# led.net
KiCad netlist of a schematic drawn in Altium Designer
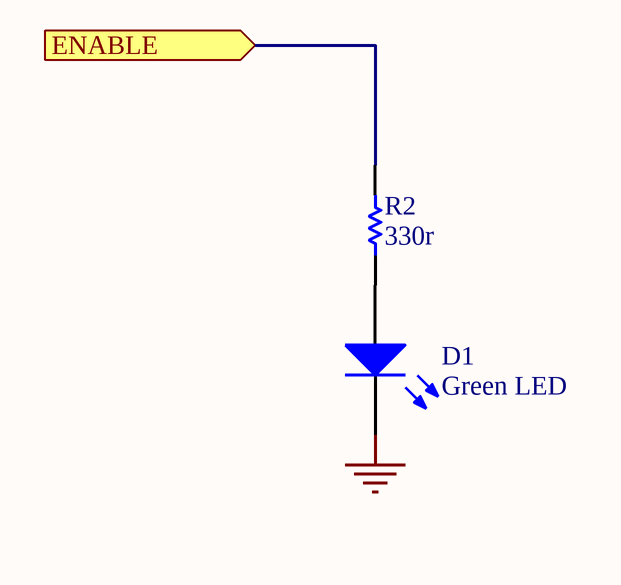
[diagram p0: led.SchDoc]

(export (version "E")
  (design (tool "Eeschema 10.0.6"))
  (components
    (comp (ref "D1")
      (value "Green LED")
      (footprint "LED 0805")
      (description "Typical INFRARED GaAs LED")
      (fields (field (name "PUBLISHER") "Altium Limited"))
      (libsource (lib "Miscellaneous Devices") (part "LED0"))
    )
    (comp (ref "R2")
      (value "330r")
      (footprint "RESC1608N")
      (description "Resistor")
      (fields (field (name "PUBLISHER") "Altium Limited"))
      (libsource (lib "Miscellaneous Devices") (part "Res1"))
    )
  )
  (nets
    (net (code "1") (name "/ENABLE") (class "Default")
      (node (ref "R2") (pin "2") (pinfunction "2_2") (pintype "passive"))
    )
    (net (code "2") (name "GND") (class "Default")
      (node (ref "D1") (pin "2") (pinfunction "K_2") (pintype "passive"))
    )
    (net (code "3") (name "Net-(D1-A)") (class "Default")
      (node (ref "D1") (pin "1") (pinfunction "A_1") (pintype "passive"))
      (node (ref "R2") (pin "1") (pinfunction "1_1") (pintype "passive"))
    )
  )
)
